# EQ.net
KiCad netlist of a schematic drawn in Altium Designer
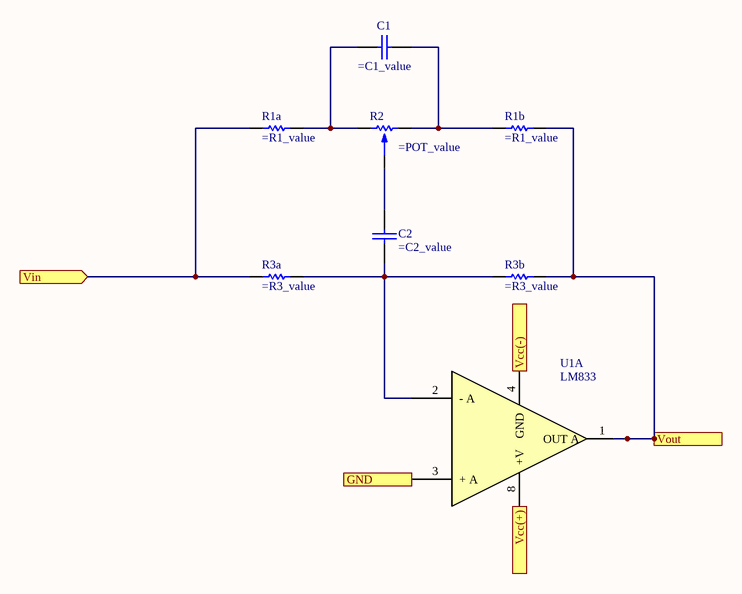
[diagram p0: EQ.SchDoc]

(export (version "E")
  (design (tool "Eeschema 10.0.6"))
  (components
    (comp (ref "C1") (value "~") (footprint "0805") (libsource (lib "LIBEBAL") (part "CAP")))
    (comp (ref "C2") (value "~") (footprint "0805") (libsource (lib "LIBEBAL") (part "CAP")))
    (comp (ref "R1a") (value "~") (footprint "0805") (libsource (lib "LIBEBAL") (part "RES")))
    (comp (ref "R1b") (value "~") (footprint "0805") (libsource (lib "LIBEBAL") (part "RES")))
    (comp (ref "R2")
      (value "~")
      (footprint "POTENCIOMETRO")
      (libsource (lib "LIBEBAL") (part "POTENCIOMETRO"))
    )
    (comp (ref "R3a") (value "~") (footprint "0805") (libsource (lib "LIBEBAL") (part "RES")))
    (comp (ref "R3b") (value "~") (footprint "0805") (libsource (lib "LIBEBAL") (part "RES")))
    (comp (ref "U1")
      (value "LM833")
      (footprint "DIP8")
      (description "Dual Audio Operational Amplifier")
      (libsource (lib "LIBEBAL") (part "LM833"))
    )
  )
  (nets
    (net (code "1") (name "/GND") (class "Default")
      (node (ref "U1") (pin "3") (pinfunction "+_A_3") (pintype "passive"))
    )
    (net (code "2") (name "/Vcc(+)") (class "Default")
      (node (ref "U1") (pin "8") (pinfunction "+V_8") (pintype "passive"))
    )
    (net (code "3") (name "/Vcc(-)") (class "Default")
      (node (ref "U1") (pin "4") (pinfunction "GND_4") (pintype "passive"))
    )
    (net (code "4") (name "/Vin") (class "Default")
      (node (ref "R1a") (pin "1") (pinfunction "1_1") (pintype "passive"))
      (node (ref "R3a") (pin "1") (pinfunction "1_1") (pintype "passive"))
    )
    (net (code "5") (name "/Vout") (class "Default")
      (node (ref "R1b") (pin "2") (pinfunction "2_2") (pintype "passive"))
      (node (ref "R3b") (pin "2") (pinfunction "2_2") (pintype "passive"))
      (node (ref "U1") (pin "1") (pinfunction "OUT_A_1") (pintype "passive"))
    )
    (net (code "6") (name "Net-(C1-Pad1)") (class "Default")
      (node (ref "C1") (pin "1") (pinfunction "1_1") (pintype "passive"))
      (node (ref "R1a") (pin "2") (pinfunction "2_2") (pintype "passive"))
      (node (ref "R2") (pin "3") (pinfunction "3_3") (pintype "passive"))
    )
    (net (code "7") (name "Net-(C1-Pad2)") (class "Default")
      (node (ref "C1") (pin "2") (pinfunction "2_2") (pintype "passive"))
      (node (ref "R1b") (pin "1") (pinfunction "1_1") (pintype "passive"))
      (node (ref "R2") (pin "1") (pinfunction "1_1") (pintype "passive"))
    )
    (net (code "8") (name "Net-(C2-Pad1)") (class "Default")
      (node (ref "C2") (pin "1") (pinfunction "1_1") (pintype "passive"))
      (node (ref "R2") (pin "2") (pinfunction "2_2") (pintype "passive"))
    )
    (net (code "9") (name "Net-(U1A--_A)") (class "Default")
      (node (ref "C2") (pin "2") (pinfunction "2_2") (pintype "passive"))
      (node (ref "R3a") (pin "2") (pinfunction "2_2") (pintype "passive"))
      (node (ref "R3b") (pin "1") (pinfunction "1_1") (pintype "passive"))
      (node (ref "U1") (pin "2") (pinfunction "-_A_2") (pintype "passive"))
    )
  )
)
